# NTC.net
KiCad netlist of a schematic drawn in Altium Designer
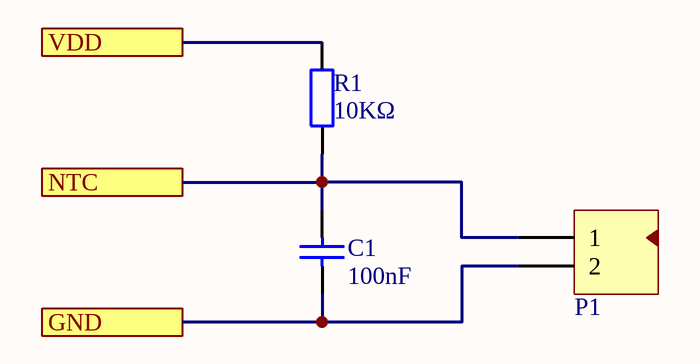
[diagram p0: NTC.SchDoc]

(export (version "E")
  (design (tool "Eeschema 10.0.6"))
  (components
    (comp (ref "C1")
      (value "100nF")
      (footprint "LC-0603_C")
      (description "贴片电容")
      (libsource (lib "Miscellaneous Devices LC") (part "0603 100nF (104) 10% 50V"))
    )
    (comp (ref "P1")
      (value "Header 2")
      (footprint "1.27mm*2_via")
      (description "接插件")
      (fields (field (name "PUBLISHER") "Altium Limited"))
      (libsource (lib "user_Library") (part "Header 2"))
    )
    (comp (ref "R1")
      (value "10KΩ")
      (footprint "LC-0603_R")
      (description "贴片电阻")
      (libsource (lib "Miscellaneous Devices LC") (part "0603 10KΩ (1002) 1%"))
    )
  )
  (nets
    (net (code "1") (name "/GND") (class "Default")
      (node (ref "C1") (pin "1") (pinfunction "1_1") (pintype "passive"))
      (node (ref "P1") (pin "2") (pinfunction "2_2") (pintype "passive"))
    )
    (net (code "2") (name "/NTC") (class "Default")
      (node (ref "C1") (pin "2") (pinfunction "2_2") (pintype "passive"))
      (node (ref "P1") (pin "1") (pinfunction "1_1") (pintype "passive"))
      (node (ref "R1") (pin "1") (pinfunction "1_1") (pintype "passive"))
    )
    (net (code "3") (name "/VDD") (class "Default")
      (node (ref "R1") (pin "2") (pinfunction "2_2") (pintype "passive"))
    )
  )
)
